# RomeBoardV1_2.net
KiCad netlist of a schematic drawn in EAGLE
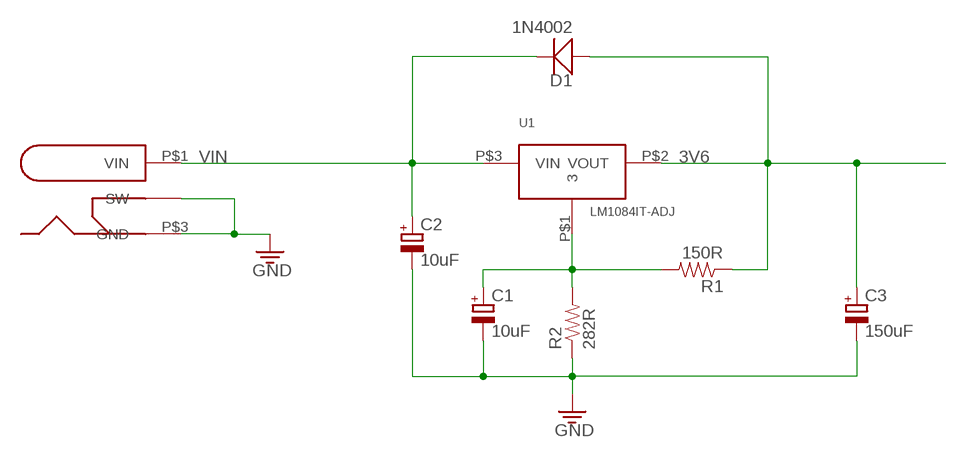
[diagram p0: schematic, sheet 1]
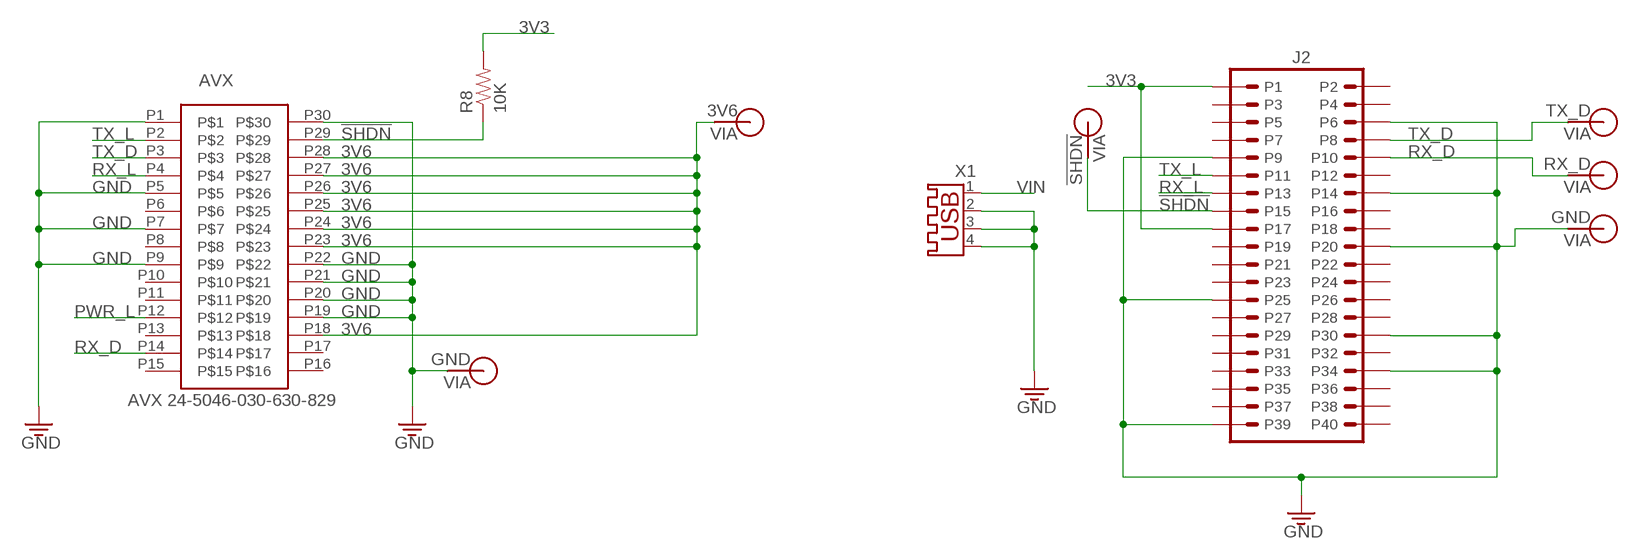
[diagram p1: schematic, sheet 2]
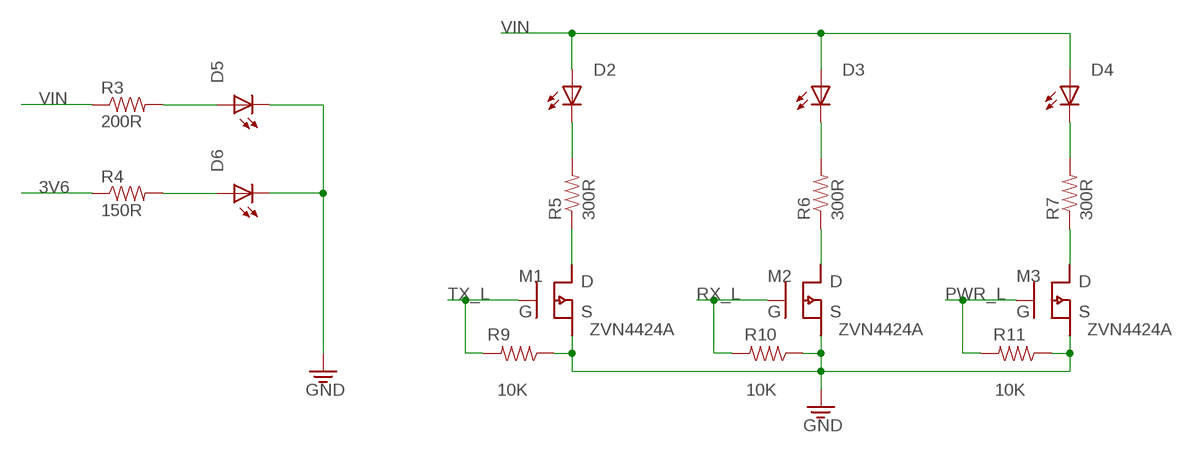
[diagram p2: schematic, sheet 3]
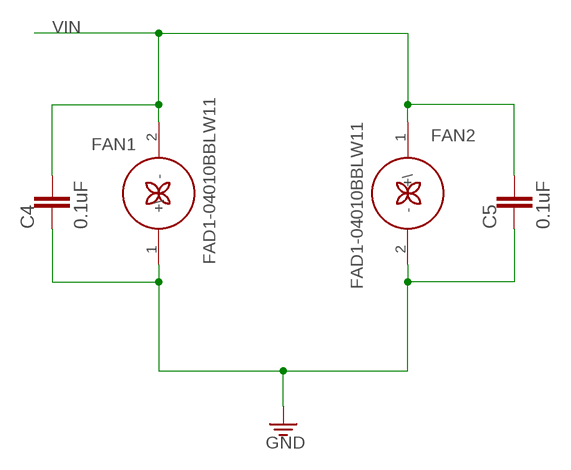
[diagram p3: schematic, sheet 4]

(export (version "E")
  (design (tool "Eeschema 10.0.6"))
  (components
    (comp (ref "AVX")
      (value "AVX-24-5046-030-630-829")
      (footprint "eagle-import:AVX-24-5046-630-829")
      (libsource (lib "eagle-import") (part "AVX-24-5046-030-630-829"))
    )
    (comp (ref "J2")
      (value "RASPBERRY-PI-HEADER")
      (footprint "eagle-import:HEADER-20X02")
      (libsource (lib "eagle-import") (part "RASPBERRY-PI-HEADER"))
    )
    (comp (ref "R8")
      (value "10K")
      (footprint "eagle-import:AXIAL-0.4")
      (libsource (lib "eagle-import") (part "RESISTOR-PTH0.4"))
    )
    (comp (ref "V1")
      (value "TX_D")
      (footprint "eagle-import:VIA-60MIL")
      (libsource (lib "eagle-import") (part "VIA-60MIL"))
    )
    (comp (ref "V2")
      (value "RX_D")
      (footprint "eagle-import:VIA-60MIL")
      (libsource (lib "eagle-import") (part "VIA-60MIL"))
    )
    (comp (ref "V3")
      (value "GND")
      (footprint "eagle-import:VIA-60MIL")
      (libsource (lib "eagle-import") (part "VIA-60MIL"))
    )
    (comp (ref "V4")
      (value "GND")
      (footprint "eagle-import:VIA-120MIL")
      (libsource (lib "eagle-import") (part "VIA-120MIL"))
    )
    (comp (ref "V5")
      (value "3V6")
      (footprint "eagle-import:VIA-120MIL")
      (libsource (lib "eagle-import") (part "VIA-120MIL"))
    )
    (comp (ref "V6")
      (value "!SHDN")
      (footprint "eagle-import:VIA-60MIL")
      (libsource (lib "eagle-import") (part "VIA-60MIL"))
    )
    (comp (ref "X1")
      (value "USB-A003")
      (footprint "eagle-import:USB-A003")
      (libsource (lib "eagle-import") (part "USB-A003"))
    )
    (comp (ref "D2")
      (value "LEDTHRU-HOLE-CONNECTOR")
      (footprint "eagle-import:1X2-POL")
      (libsource (lib "eagle-import") (part "LEDTHRU-HOLE-CONNECTOR"))
    )
    (comp (ref "D3")
      (value "LEDTHRU-HOLE-CONNECTOR")
      (footprint "eagle-import:1X2-POL")
      (libsource (lib "eagle-import") (part "LEDTHRU-HOLE-CONNECTOR"))
    )
    (comp (ref "D4")
      (value "LEDTHRU-HOLE-CONNECTOR")
      (footprint "eagle-import:1X2-POL")
      (libsource (lib "eagle-import") (part "LEDTHRU-HOLE-CONNECTOR"))
    )
    (comp (ref "D5")
      (value "LEDTHRU-HOLE-CONNECTOR")
      (footprint "eagle-import:1X2-POL")
      (libsource (lib "eagle-import") (part "LEDTHRU-HOLE-CONNECTOR"))
    )
    (comp (ref "D6")
      (value "LEDTHRU-HOLE-CONNECTOR")
      (footprint "eagle-import:1X2-POL")
      (libsource (lib "eagle-import") (part "LEDTHRU-HOLE-CONNECTOR"))
    )
    (comp (ref "M1")
      (value "ZVN4424A")
      (footprint "eagle-import:TO-923-MOS")
      (libsource (lib "eagle-import") (part "ZVN4424A"))
    )
    (comp (ref "M2")
      (value "ZVN4424A")
      (footprint "eagle-import:TO-923-MOS")
      (libsource (lib "eagle-import") (part "ZVN4424A"))
    )
    (comp (ref "M3")
      (value "ZVN4424A")
      (footprint "eagle-import:TO-923-MOS")
      (libsource (lib "eagle-import") (part "ZVN4424A"))
    )
    (comp (ref "R3")
      (value "200R")
      (footprint "eagle-import:AXIAL-0.4")
      (libsource (lib "eagle-import") (part "RESISTOR-PTH0.4"))
    )
    (comp (ref "R4")
      (value "150R")
      (footprint "eagle-import:AXIAL-0.4")
      (libsource (lib "eagle-import") (part "RESISTOR-PTH0.4"))
    )
    (comp (ref "R5")
      (value "300R")
      (footprint "eagle-import:AXIAL-0.4")
      (libsource (lib "eagle-import") (part "RESISTOR-PTH0.4"))
    )
    (comp (ref "R6")
      (value "300R")
      (footprint "eagle-import:AXIAL-0.4")
      (libsource (lib "eagle-import") (part "RESISTOR-PTH0.4"))
    )
    (comp (ref "R7")
      (value "300R")
      (footprint "eagle-import:AXIAL-0.4")
      (libsource (lib "eagle-import") (part "RESISTOR-PTH0.4"))
    )
    (comp (ref "R9")
      (value "10K")
      (footprint "eagle-import:AXIAL-0.4")
      (libsource (lib "eagle-import") (part "RESISTOR-PTH0.4"))
    )
    (comp (ref "R10")
      (value "10K")
      (footprint "eagle-import:AXIAL-0.4")
      (libsource (lib "eagle-import") (part "RESISTOR-PTH0.4"))
    )
    (comp (ref "R11")
      (value "10K")
      (footprint "eagle-import:AXIAL-0.4")
      (libsource (lib "eagle-import") (part "RESISTOR-PTH0.4"))
    )
    (comp (ref "C4")
      (value "0.1uF")
      (footprint "eagle-import:C050-025X075")
      (libsource (lib "eagle-import") (part "CAP5MM-THRU-HOLE"))
    )
    (comp (ref "C5")
      (value "0.1uF")
      (footprint "eagle-import:C050-025X075")
      (libsource (lib "eagle-import") (part "CAP5MM-THRU-HOLE"))
    )
    (comp (ref "FAN1")
      (value "FAD1-04010BBLW11")
      (footprint "eagle-import:1X2-POL")
      (libsource (lib "eagle-import") (part "FAD1-04010BBLW11"))
    )
    (comp (ref "FAN2")
      (value "FAD1-04010BBLW11")
      (footprint "eagle-import:1X2-POL")
      (libsource (lib "eagle-import") (part "FAD1-04010BBLW11"))
    )
    (comp (ref "C1")
      (value "10uF")
      (footprint "eagle-import:E2,5-7")
      (libsource (lib "eagle-import") (part "CPOL-EUE2.5-7"))
    )
    (comp (ref "C2")
      (value "10uF")
      (footprint "eagle-import:E2,5-7")
      (libsource (lib "eagle-import") (part "CPOL-EUE2.5-7"))
    )
    (comp (ref "C3")
      (value "150uF")
      (footprint "eagle-import:E5-13")
      (libsource (lib "eagle-import") (part "CPOL-EUE5-13"))
    )
    (comp (ref "D1")
      (value "1N4002")
      (footprint "eagle-import:DO-201AD")
      (libsource (lib "eagle-import") (part "1N4002"))
    )
    (comp (ref "R1")
      (value "150R")
      (footprint "eagle-import:AXIAL-0.4")
      (libsource (lib "eagle-import") (part "RESISTOR-PTH0.4"))
    )
    (comp (ref "R2")
      (value "282R")
      (footprint "eagle-import:AXIAL-0.4")
      (libsource (lib "eagle-import") (part "RESISTOR-PTH0.4"))
    )
    (comp (ref "U$2")
      (value "PJ-002A")
      (footprint "eagle-import:PJ-002A")
      (libsource (lib "eagle-import") (part "PJ-002A"))
    )
    (comp (ref "U1")
      (value "LM1084IT-ADJ")
      (footprint "eagle-import:TO-220-507302B00000G")
      (libsource (lib "eagle-import") (part "LM1084IT-ADJ"))
    )
  )
  (nets
    (net (code "1") (name "3V3") (class "Default")
      (node (ref "J2") (pin "P1") (pinfunction "P1_P1") (pintype "passive"))
      (node (ref "J2") (pin "P17") (pinfunction "P17_P17") (pintype "passive"))
      (node (ref "R8") (pin "2") (pinfunction "2_2") (pintype "passive"))
    )
    (net (code "2") (name "3V6") (class "Default")
      (node (ref "AVX") (pin "P18") (pinfunction "P$18_P18") (pintype "bidirectional"))
      (node (ref "AVX") (pin "P23") (pinfunction "P$23_P23") (pintype "bidirectional"))
      (node (ref "AVX") (pin "P24") (pinfunction "P$24_P24") (pintype "bidirectional"))
      (node (ref "AVX") (pin "P25") (pinfunction "P$25_P25") (pintype "bidirectional"))
      (node (ref "AVX") (pin "P26") (pinfunction "P$26_P26") (pintype "bidirectional"))
      (node (ref "AVX") (pin "P27") (pinfunction "P$27_P27") (pintype "bidirectional"))
      (node (ref "AVX") (pin "P28") (pinfunction "P$28_P28") (pintype "bidirectional"))
      (node (ref "C3") (pin "+") (pinfunction "+_+") (pintype "passive"))
      (node (ref "D1") (pin "P$1") (pinfunction "A_P$1") (pintype "bidirectional"))
      (node (ref "R1") (pin "1") (pinfunction "1_1") (pintype "passive"))
      (node (ref "R4") (pin "1") (pinfunction "1_1") (pintype "passive"))
      (node (ref "U1") (pin "P$2") (pinfunction "VOUT_P$2") (pintype "bidirectional"))
      (node (ref "V5") (pin "P$1") (pinfunction "P$1_P$1") (pintype "bidirectional"))
    )
    (net (code "3") (name "GND") (class "Default")
      (node (ref "AVX") (pin "P1") (pinfunction "P$1_P1") (pintype "bidirectional"))
      (node (ref "AVX") (pin "P19") (pinfunction "P$19_P19") (pintype "bidirectional"))
      (node (ref "AVX") (pin "P20") (pinfunction "P$20_P20") (pintype "bidirectional"))
      (node (ref "AVX") (pin "P21") (pinfunction "P$21_P21") (pintype "bidirectional"))
      (node (ref "AVX") (pin "P22") (pinfunction "P$22_P22") (pintype "bidirectional"))
      (node (ref "AVX") (pin "P30") (pinfunction "P$30_P30") (pintype "bidirectional"))
      (node (ref "AVX") (pin "P5") (pinfunction "P$5_P5") (pintype "bidirectional"))
      (node (ref "AVX") (pin "P7") (pinfunction "P$7_P7") (pintype "bidirectional"))
      (node (ref "AVX") (pin "P9") (pinfunction "P$9_P9") (pintype "bidirectional"))
      (node (ref "C1") (pin "-") (pinfunction "-_-") (pintype "passive"))
      (node (ref "C2") (pin "-") (pinfunction "-_-") (pintype "passive"))
      (node (ref "C3") (pin "-") (pinfunction "-_-") (pintype "passive"))
      (node (ref "C4") (pin "2") (pinfunction "P$2_2") (pintype "passive"))
      (node (ref "C5") (pin "2") (pinfunction "P$2_2") (pintype "passive"))
      (node (ref "D5") (pin "2") (pinfunction "C_2") (pintype "passive"))
      (node (ref "D6") (pin "2") (pinfunction "C_2") (pintype "passive"))
      (node (ref "FAN1") (pin "1") (pinfunction "+\\_1") (pintype "bidirectional"))
      (node (ref "FAN2") (pin "2") (pinfunction "-_2") (pintype "bidirectional"))
      (node (ref "J2") (pin "P14") (pinfunction "P14_P14") (pintype "passive"))
      (node (ref "J2") (pin "P20") (pinfunction "P20_P20") (pintype "passive"))
      (node (ref "J2") (pin "P25") (pinfunction "P25_P25") (pintype "passive"))
      (node (ref "J2") (pin "P30") (pinfunction "P30_P30") (pintype "passive"))
      (node (ref "J2") (pin "P34") (pinfunction "P34_P34") (pintype "passive"))
      (node (ref "J2") (pin "P39") (pinfunction "P39_P39") (pintype "passive"))
      (node (ref "J2") (pin "P6") (pinfunction "P6_P6") (pintype "passive"))
      (node (ref "J2") (pin "P9") (pinfunction "P9_P9") (pintype "passive"))
      (node (ref "M1") (pin "3") (pinfunction "S_3") (pintype "bidirectional"))
      (node (ref "M2") (pin "3") (pinfunction "S_3") (pintype "bidirectional"))
      (node (ref "M3") (pin "3") (pinfunction "S_3") (pintype "bidirectional"))
      (node (ref "R10") (pin "1") (pinfunction "1_1") (pintype "passive"))
      (node (ref "R11") (pin "1") (pinfunction "1_1") (pintype "passive"))
      (node (ref "R2") (pin "1") (pinfunction "1_1") (pintype "passive"))
      (node (ref "R9") (pin "1") (pinfunction "1_1") (pintype "passive"))
      (node (ref "U$2") (pin "P$2") (pinfunction "SW_P$2") (pintype "bidirectional"))
      (node (ref "U$2") (pin "P$3") (pinfunction "GND_P$3") (pintype "bidirectional"))
      (node (ref "V3") (pin "P$1") (pinfunction "P$1_P$1") (pintype "bidirectional"))
      (node (ref "V4") (pin "P$1") (pinfunction "P$1_P$1") (pintype "bidirectional"))
      (node (ref "X1") (pin "2") (pinfunction "2_2") (pintype "passive"))
      (node (ref "X1") (pin "3") (pinfunction "3_3") (pintype "passive"))
      (node (ref "X1") (pin "4") (pinfunction "4_4") (pintype "passive"))
    )
    (net (code "4") (name "Net-(D2-C)") (class "Default")
      (node (ref "D2") (pin "2") (pinfunction "C_2") (pintype "passive"))
      (node (ref "R5") (pin "2") (pinfunction "2_2") (pintype "passive"))
    )
    (net (code "5") (name "Net-(D3-C)") (class "Default")
      (node (ref "D3") (pin "2") (pinfunction "C_2") (pintype "passive"))
      (node (ref "R6") (pin "2") (pinfunction "2_2") (pintype "passive"))
    )
    (net (code "6") (name "Net-(D4-C)") (class "Default")
      (node (ref "D4") (pin "2") (pinfunction "C_2") (pintype "passive"))
      (node (ref "R7") (pin "2") (pinfunction "2_2") (pintype "passive"))
    )
    (net (code "7") (name "Net-(D5-A)") (class "Default")
      (node (ref "D5") (pin "1") (pinfunction "A_1") (pintype "passive"))
      (node (ref "R3") (pin "2") (pinfunction "2_2") (pintype "passive"))
    )
    (net (code "8") (name "Net-(D6-A)") (class "Default")
      (node (ref "D6") (pin "1") (pinfunction "A_1") (pintype "passive"))
      (node (ref "R4") (pin "2") (pinfunction "2_2") (pintype "passive"))
    )
    (net (code "9") (name "Net-(M1-D)") (class "Default")
      (node (ref "M1") (pin "1") (pinfunction "D_1") (pintype "bidirectional"))
      (node (ref "R5") (pin "1") (pinfunction "1_1") (pintype "passive"))
    )
    (net (code "10") (name "Net-(M2-D)") (class "Default")
      (node (ref "M2") (pin "1") (pinfunction "D_1") (pintype "bidirectional"))
      (node (ref "R6") (pin "1") (pinfunction "1_1") (pintype "passive"))
    )
    (net (code "11") (name "Net-(M3-D)") (class "Default")
      (node (ref "M3") (pin "1") (pinfunction "D_1") (pintype "bidirectional"))
      (node (ref "R7") (pin "1") (pinfunction "1_1") (pintype "passive"))
    )
    (net (code "12") (name "Net-(U1-3)") (class "Default")
      (node (ref "C1") (pin "+") (pinfunction "+_+") (pintype "passive"))
      (node (ref "R1") (pin "2") (pinfunction "2_2") (pintype "passive"))
      (node (ref "R2") (pin "2") (pinfunction "2_2") (pintype "passive"))
      (node (ref "U1") (pin "P$1") (pinfunction "3_P$1") (pintype "bidirectional"))
    )
    (net (code "13") (name "PWR_L") (class "Default")
      (node (ref "AVX") (pin "P12") (pinfunction "P$12_P12") (pintype "bidirectional"))
      (node (ref "M3") (pin "2") (pinfunction "G_2") (pintype "bidirectional"))
      (node (ref "R11") (pin "2") (pinfunction "2_2") (pintype "passive"))
    )
    (net (code "14") (name "RX_D") (class "Default")
      (node (ref "AVX") (pin "P14") (pinfunction "P$14_P14") (pintype "bidirectional"))
      (node (ref "J2") (pin "P10") (pinfunction "P10_P10") (pintype "passive"))
      (node (ref "V2") (pin "P$1") (pinfunction "P$1_P$1") (pintype "bidirectional"))
    )
    (net (code "15") (name "RX_L") (class "Default")
      (node (ref "AVX") (pin "P4") (pinfunction "P$4_P4") (pintype "bidirectional"))
      (node (ref "J2") (pin "P13") (pinfunction "P13_P13") (pintype "passive"))
      (node (ref "M2") (pin "2") (pinfunction "G_2") (pintype "bidirectional"))
      (node (ref "R10") (pin "2") (pinfunction "2_2") (pintype "passive"))
    )
    (net (code "16") (name "TX_D") (class "Default")
      (node (ref "AVX") (pin "P3") (pinfunction "P$3_P3") (pintype "bidirectional"))
      (node (ref "J2") (pin "P8") (pinfunction "P8_P8") (pintype "passive"))
      (node (ref "V1") (pin "P$1") (pinfunction "P$1_P$1") (pintype "bidirectional"))
    )
    (net (code "17") (name "TX_L") (class "Default")
      (node (ref "AVX") (pin "P2") (pinfunction "P$2_P2") (pintype "bidirectional"))
      (node (ref "J2") (pin "P11") (pinfunction "P11_P11") (pintype "passive"))
      (node (ref "M1") (pin "2") (pinfunction "G_2") (pintype "bidirectional"))
      (node (ref "R9") (pin "2") (pinfunction "2_2") (pintype "passive"))
    )
    (net (code "18") (name "VIN") (class "Default")
      (node (ref "C2") (pin "+") (pinfunction "+_+") (pintype "passive"))
      (node (ref "C4") (pin "1") (pinfunction "P$1_1") (pintype "passive"))
      (node (ref "C5") (pin "1") (pinfunction "P$1_1") (pintype "passive"))
      (node (ref "D1") (pin "P$2") (pinfunction "C_P$2") (pintype "bidirectional"))
      (node (ref "D2") (pin "1") (pinfunction "A_1") (pintype "passive"))
      (node (ref "D3") (pin "1") (pinfunction "A_1") (pintype "passive"))
      (node (ref "D4") (pin "1") (pinfunction "A_1") (pintype "passive"))
      (node (ref "FAN1") (pin "2") (pinfunction "-_2") (pintype "bidirectional"))
      (node (ref "FAN2") (pin "1") (pinfunction "+\\_1") (pintype "bidirectional"))
      (node (ref "R3") (pin "1") (pinfunction "1_1") (pintype "passive"))
      (node (ref "U$2") (pin "P$1") (pinfunction "VIN_P$1") (pintype "bidirectional"))
      (node (ref "U1") (pin "P$3") (pinfunction "VIN_P$3") (pintype "bidirectional"))
      (node (ref "X1") (pin "1") (pinfunction "1_1") (pintype "passive"))
    )
    (net (code "19") (name "unconnected-(AVX-P$6-PadP6)") (class "Default")
      (node (ref "AVX") (pin "P6") (pinfunction "P$6_P6") (pintype "bidirectional"))
    )
    (net (code "20") (name "unconnected-(AVX-P$8-PadP8)") (class "Default")
      (node (ref "AVX") (pin "P8") (pinfunction "P$8_P8") (pintype "bidirectional"))
    )
    (net (code "21") (name "unconnected-(AVX-P$10-PadP10)") (class "Default")
      (node (ref "AVX") (pin "P10") (pinfunction "P$10_P10") (pintype "bidirectional"))
    )
    (net (code "22") (name "unconnected-(AVX-P$11-PadP11)") (class "Default")
      (node (ref "AVX") (pin "P11") (pinfunction "P$11_P11") (pintype "bidirectional"))
    )
    (net (code "23") (name "unconnected-(AVX-P$13-PadP13)") (class "Default")
      (node (ref "AVX") (pin "P13") (pinfunction "P$13_P13") (pintype "bidirectional"))
    )
    (net (code "24") (name "unconnected-(AVX-P$15-PadP15)") (class "Default")
      (node (ref "AVX") (pin "P15") (pinfunction "P$15_P15") (pintype "bidirectional"))
    )
    (net (code "25") (name "unconnected-(AVX-P$16-PadP16)") (class "Default")
      (node (ref "AVX") (pin "P16") (pinfunction "P$16_P16") (pintype "bidirectional"))
    )
    (net (code "26") (name "unconnected-(AVX-P$17-PadP17)") (class "Default")
      (node (ref "AVX") (pin "P17") (pinfunction "P$17_P17") (pintype "bidirectional"))
    )
    (net (code "27") (name "unconnected-(J2-PadP2)") (class "Default")
      (node (ref "J2") (pin "P2") (pinfunction "P2_P2") (pintype "passive"))
    )
    (net (code "28") (name "unconnected-(J2-PadP3)") (class "Default")
      (node (ref "J2") (pin "P3") (pinfunction "P3_P3") (pintype "passive"))
    )
    (net (code "29") (name "unconnected-(J2-PadP4)") (class "Default")
      (node (ref "J2") (pin "P4") (pinfunction "P4_P4") (pintype "passive"))
    )
    (net (code "30") (name "unconnected-(J2-PadP5)") (class "Default")
      (node (ref "J2") (pin "P5") (pinfunction "P5_P5") (pintype "passive"))
    )
    (net (code "31") (name "unconnected-(J2-PadP7)") (class "Default")
      (node (ref "J2") (pin "P7") (pinfunction "P7_P7") (pintype "passive"))
    )
    (net (code "32") (name "unconnected-(J2-PadP12)") (class "Default")
      (node (ref "J2") (pin "P12") (pinfunction "P12_P12") (pintype "passive"))
    )
    (net (code "33") (name "unconnected-(J2-PadP16)") (class "Default")
      (node (ref "J2") (pin "P16") (pinfunction "P16_P16") (pintype "passive"))
    )
    (net (code "34") (name "unconnected-(J2-PadP18)") (class "Default")
      (node (ref "J2") (pin "P18") (pinfunction "P18_P18") (pintype "passive"))
    )
    (net (code "35") (name "unconnected-(J2-PadP19)") (class "Default")
      (node (ref "J2") (pin "P19") (pinfunction "P19_P19") (pintype "passive"))
    )
    (net (code "36") (name "unconnected-(J2-PadP21)") (class "Default")
      (node (ref "J2") (pin "P21") (pinfunction "P21_P21") (pintype "passive"))
    )
    (net (code "37") (name "unconnected-(J2-PadP22)") (class "Default")
      (node (ref "J2") (pin "P22") (pinfunction "P22_P22") (pintype "passive"))
    )
    (net (code "38") (name "unconnected-(J2-PadP23)") (class "Default")
      (node (ref "J2") (pin "P23") (pinfunction "P23_P23") (pintype "passive"))
    )
    (net (code "39") (name "unconnected-(J2-PadP24)") (class "Default")
      (node (ref "J2") (pin "P24") (pinfunction "P24_P24") (pintype "passive"))
    )
    (net (code "40") (name "unconnected-(J2-PadP26)") (class "Default")
      (node (ref "J2") (pin "P26") (pinfunction "P26_P26") (pintype "passive"))
    )
    (net (code "41") (name "unconnected-(J2-PadP27)") (class "Default")
      (node (ref "J2") (pin "P27") (pinfunction "P27_P27") (pintype "passive"))
    )
    (net (code "42") (name "unconnected-(J2-PadP28)") (class "Default")
      (node (ref "J2") (pin "P28") (pinfunction "P28_P28") (pintype "passive"))
    )
    (net (code "43") (name "unconnected-(J2-PadP29)") (class "Default")
      (node (ref "J2") (pin "P29") (pinfunction "P29_P29") (pintype "passive"))
    )
    (net (code "44") (name "unconnected-(J2-PadP31)") (class "Default")
      (node (ref "J2") (pin "P31") (pinfunction "P31_P31") (pintype "passive"))
    )
    (net (code "45") (name "unconnected-(J2-PadP32)") (class "Default")
      (node (ref "J2") (pin "P32") (pinfunction "P32_P32") (pintype "passive"))
    )
    (net (code "46") (name "unconnected-(J2-PadP33)") (class "Default")
      (node (ref "J2") (pin "P33") (pinfunction "P33_P33") (pintype "passive"))
    )
    (net (code "47") (name "unconnected-(J2-PadP35)") (class "Default")
      (node (ref "J2") (pin "P35") (pinfunction "P35_P35") (pintype "passive"))
    )
    (net (code "48") (name "unconnected-(J2-PadP36)") (class "Default")
      (node (ref "J2") (pin "P36") (pinfunction "P36_P36") (pintype "passive"))
    )
    (net (code "49") (name "unconnected-(J2-PadP37)") (class "Default")
      (node (ref "J2") (pin "P37") (pinfunction "P37_P37") (pintype "passive"))
    )
    (net (code "50") (name "unconnected-(J2-PadP38)") (class "Default")
      (node (ref "J2") (pin "P38") (pinfunction "P38_P38") (pintype "passive"))
    )
    (net (code "51") (name "unconnected-(J2-PadP40)") (class "Default")
      (node (ref "J2") (pin "P40") (pinfunction "P40_P40") (pintype "passive"))
    )
    (net (code "52") (name "~{SHDN}") (class "Default")
      (node (ref "AVX") (pin "P29") (pinfunction "P$29_P29") (pintype "bidirectional"))
      (node (ref "J2") (pin "P15") (pinfunction "P15_P15") (pintype "passive"))
      (node (ref "R8") (pin "1") (pinfunction "1_1") (pintype "passive"))
      (node (ref "V6") (pin "P$1") (pinfunction "P$1_P$1") (pintype "bidirectional"))
    )
  )
)
